# bin-to-dec_tube-driver.net
KiCad netlist of a schematic drawn in EAGLE
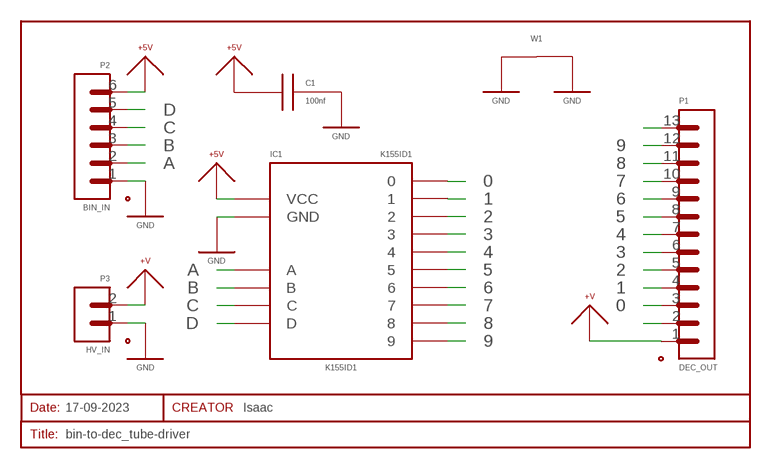
[diagram p0: schematic, sheet 1]

(export (version "E")
  (design (tool "Eeschema 10.0.6"))
  (components
    (comp (ref "C1")
      (value "100nf")
      (footprint "eagle-import:CAPACITOR_UNPOLARISED_5.08MM")
      (libsource (lib "eagle-import") (part "CAPACITOR_UNPOLARISED_5.08MM"))
    )
    (comp (ref "CREATOR")
      (value "Isaac")
      (footprint "eagle-import:INFO_T")
      (libsource (lib "eagle-import") (part "INFO_T"))
    )
    (comp (ref "IC1")
      (value "K155ID1")
      (footprint "eagle-import:16-PIN_DIP")
      (libsource (lib "eagle-import") (part "K155ID1_DIP"))
    )
    (comp (ref "P1")
      (value "DEC_OUT")
      (footprint "eagle-import:HEADER_13-PIN")
      (libsource (lib "eagle-import") (part "PORT_13-PIN_HEADER"))
    )
    (comp (ref "P2")
      (value "BIN_IN")
      (footprint "eagle-import:XH2.54_6-PIN")
      (libsource (lib "eagle-import") (part "PORT_6-PIN_XH2.54"))
    )
    (comp (ref "P3")
      (value "HV_IN")
      (footprint "eagle-import:XH2.54_2-PIN")
      (libsource (lib "eagle-import") (part "PORT_2-PIN_XH2.54"))
    )
    (comp (ref "SCHEMATIC1")
      (value "17-09-2023")
      (footprint "eagle-import:SHEET")
      (libsource (lib "eagle-import") (part "SHEET"))
    )
    (comp (ref "W1")
      (value "WIRE_7.62MM")
      (footprint "eagle-import:WIRE_7.62MM")
      (libsource (lib "eagle-import") (part "WIRE_7.62MM"))
    )
  )
  (nets
    (net (code "1") (name "+5V") (class "Default")
      (node (ref "C1") (pin "1") (pinfunction "1_1") (pintype "bidirectional"))
      (node (ref "IC1") (pin "5") (pinfunction "VCC_5") (pintype "power_in"))
      (node (ref "P2") (pin "6") (pinfunction "6_6") (pintype "bidirectional"))
    )
    (net (code "2") (name "+V") (class "Default")
      (node (ref "P1") (pin "1") (pinfunction "1_1") (pintype "bidirectional"))
      (node (ref "P3") (pin "2") (pinfunction "2_2") (pintype "bidirectional"))
    )
    (net (code "3") (name "/0") (class "Default")
      (node (ref "IC1") (pin "16") (pinfunction "0_16") (pintype "bidirectional"))
      (node (ref "P1") (pin "3") (pinfunction "3_3") (pintype "bidirectional"))
    )
    (net (code "4") (name "/1") (class "Default")
      (node (ref "IC1") (pin "15") (pinfunction "1_15") (pintype "bidirectional"))
      (node (ref "P1") (pin "4") (pinfunction "4_4") (pintype "bidirectional"))
    )
    (net (code "5") (name "/2") (class "Default")
      (node (ref "IC1") (pin "8") (pinfunction "2_8") (pintype "bidirectional"))
      (node (ref "P1") (pin "5") (pinfunction "5_5") (pintype "bidirectional"))
    )
    (net (code "6") (name "/3") (class "Default")
      (node (ref "IC1") (pin "9") (pinfunction "3_9") (pintype "bidirectional"))
      (node (ref "P1") (pin "6") (pinfunction "6_6") (pintype "bidirectional"))
    )
    (net (code "7") (name "/4") (class "Default")
      (node (ref "IC1") (pin "13") (pinfunction "4_13") (pintype "bidirectional"))
      (node (ref "P1") (pin "7") (pinfunction "7_7") (pintype "bidirectional"))
    )
    (net (code "8") (name "/5") (class "Default")
      (node (ref "IC1") (pin "14") (pinfunction "5_14") (pintype "bidirectional"))
      (node (ref "P1") (pin "8") (pinfunction "8_8") (pintype "bidirectional"))
    )
    (net (code "9") (name "/6") (class "Default")
      (node (ref "IC1") (pin "11") (pinfunction "6_11") (pintype "bidirectional"))
      (node (ref "P1") (pin "9") (pinfunction "9_9") (pintype "bidirectional"))
    )
    (net (code "10") (name "/7") (class "Default")
      (node (ref "IC1") (pin "10") (pinfunction "7_10") (pintype "bidirectional"))
      (node (ref "P1") (pin "10") (pinfunction "10_10") (pintype "bidirectional"))
    )
    (net (code "11") (name "/8") (class "Default")
      (node (ref "IC1") (pin "1") (pinfunction "8_1") (pintype "bidirectional"))
      (node (ref "P1") (pin "11") (pinfunction "11_11") (pintype "bidirectional"))
    )
    (net (code "12") (name "/9") (class "Default")
      (node (ref "IC1") (pin "2") (pinfunction "9_2") (pintype "bidirectional"))
      (node (ref "P1") (pin "12") (pinfunction "12_12") (pintype "bidirectional"))
    )
    (net (code "13") (name "/A") (class "Default")
      (node (ref "IC1") (pin "3") (pinfunction "A_3") (pintype "input"))
      (node (ref "P2") (pin "2") (pinfunction "2_2") (pintype "bidirectional"))
    )
    (net (code "14") (name "/B") (class "Default")
      (node (ref "IC1") (pin "6") (pinfunction "B_6") (pintype "input"))
      (node (ref "P2") (pin "3") (pinfunction "3_3") (pintype "bidirectional"))
    )
    (net (code "15") (name "/C") (class "Default")
      (node (ref "IC1") (pin "7") (pinfunction "C_7") (pintype "input"))
      (node (ref "P2") (pin "4") (pinfunction "4_4") (pintype "bidirectional"))
    )
    (net (code "16") (name "/D") (class "Default")
      (node (ref "IC1") (pin "4") (pinfunction "D_4") (pintype "input"))
      (node (ref "P2") (pin "5") (pinfunction "5_5") (pintype "bidirectional"))
    )
    (net (code "17") (name "GND") (class "Default")
      (node (ref "C1") (pin "2") (pinfunction "2_2") (pintype "bidirectional"))
      (node (ref "IC1") (pin "12") (pinfunction "GND_12") (pintype "power_in"))
      (node (ref "P2") (pin "1") (pinfunction "1_1") (pintype "bidirectional"))
      (node (ref "P3") (pin "1") (pinfunction "1_1") (pintype "bidirectional"))
      (node (ref "W1") (pin "1") (pinfunction "1_1") (pintype "bidirectional"))
      (node (ref "W1") (pin "2") (pinfunction "2_2") (pintype "bidirectional"))
    )
    (net (code "18") (name "unconnected-(P1-Pad2)") (class "Default")
      (node (ref "P1") (pin "2") (pinfunction "2_2") (pintype "bidirectional"))
    )
    (net (code "19") (name "unconnected-(P1-Pad13)") (class "Default")
      (node (ref "P1") (pin "13") (pinfunction "13_13") (pintype "bidirectional"))
    )
  )
)
